# Sheet1.net
KiCad netlist of a schematic drawn in Altium Designer
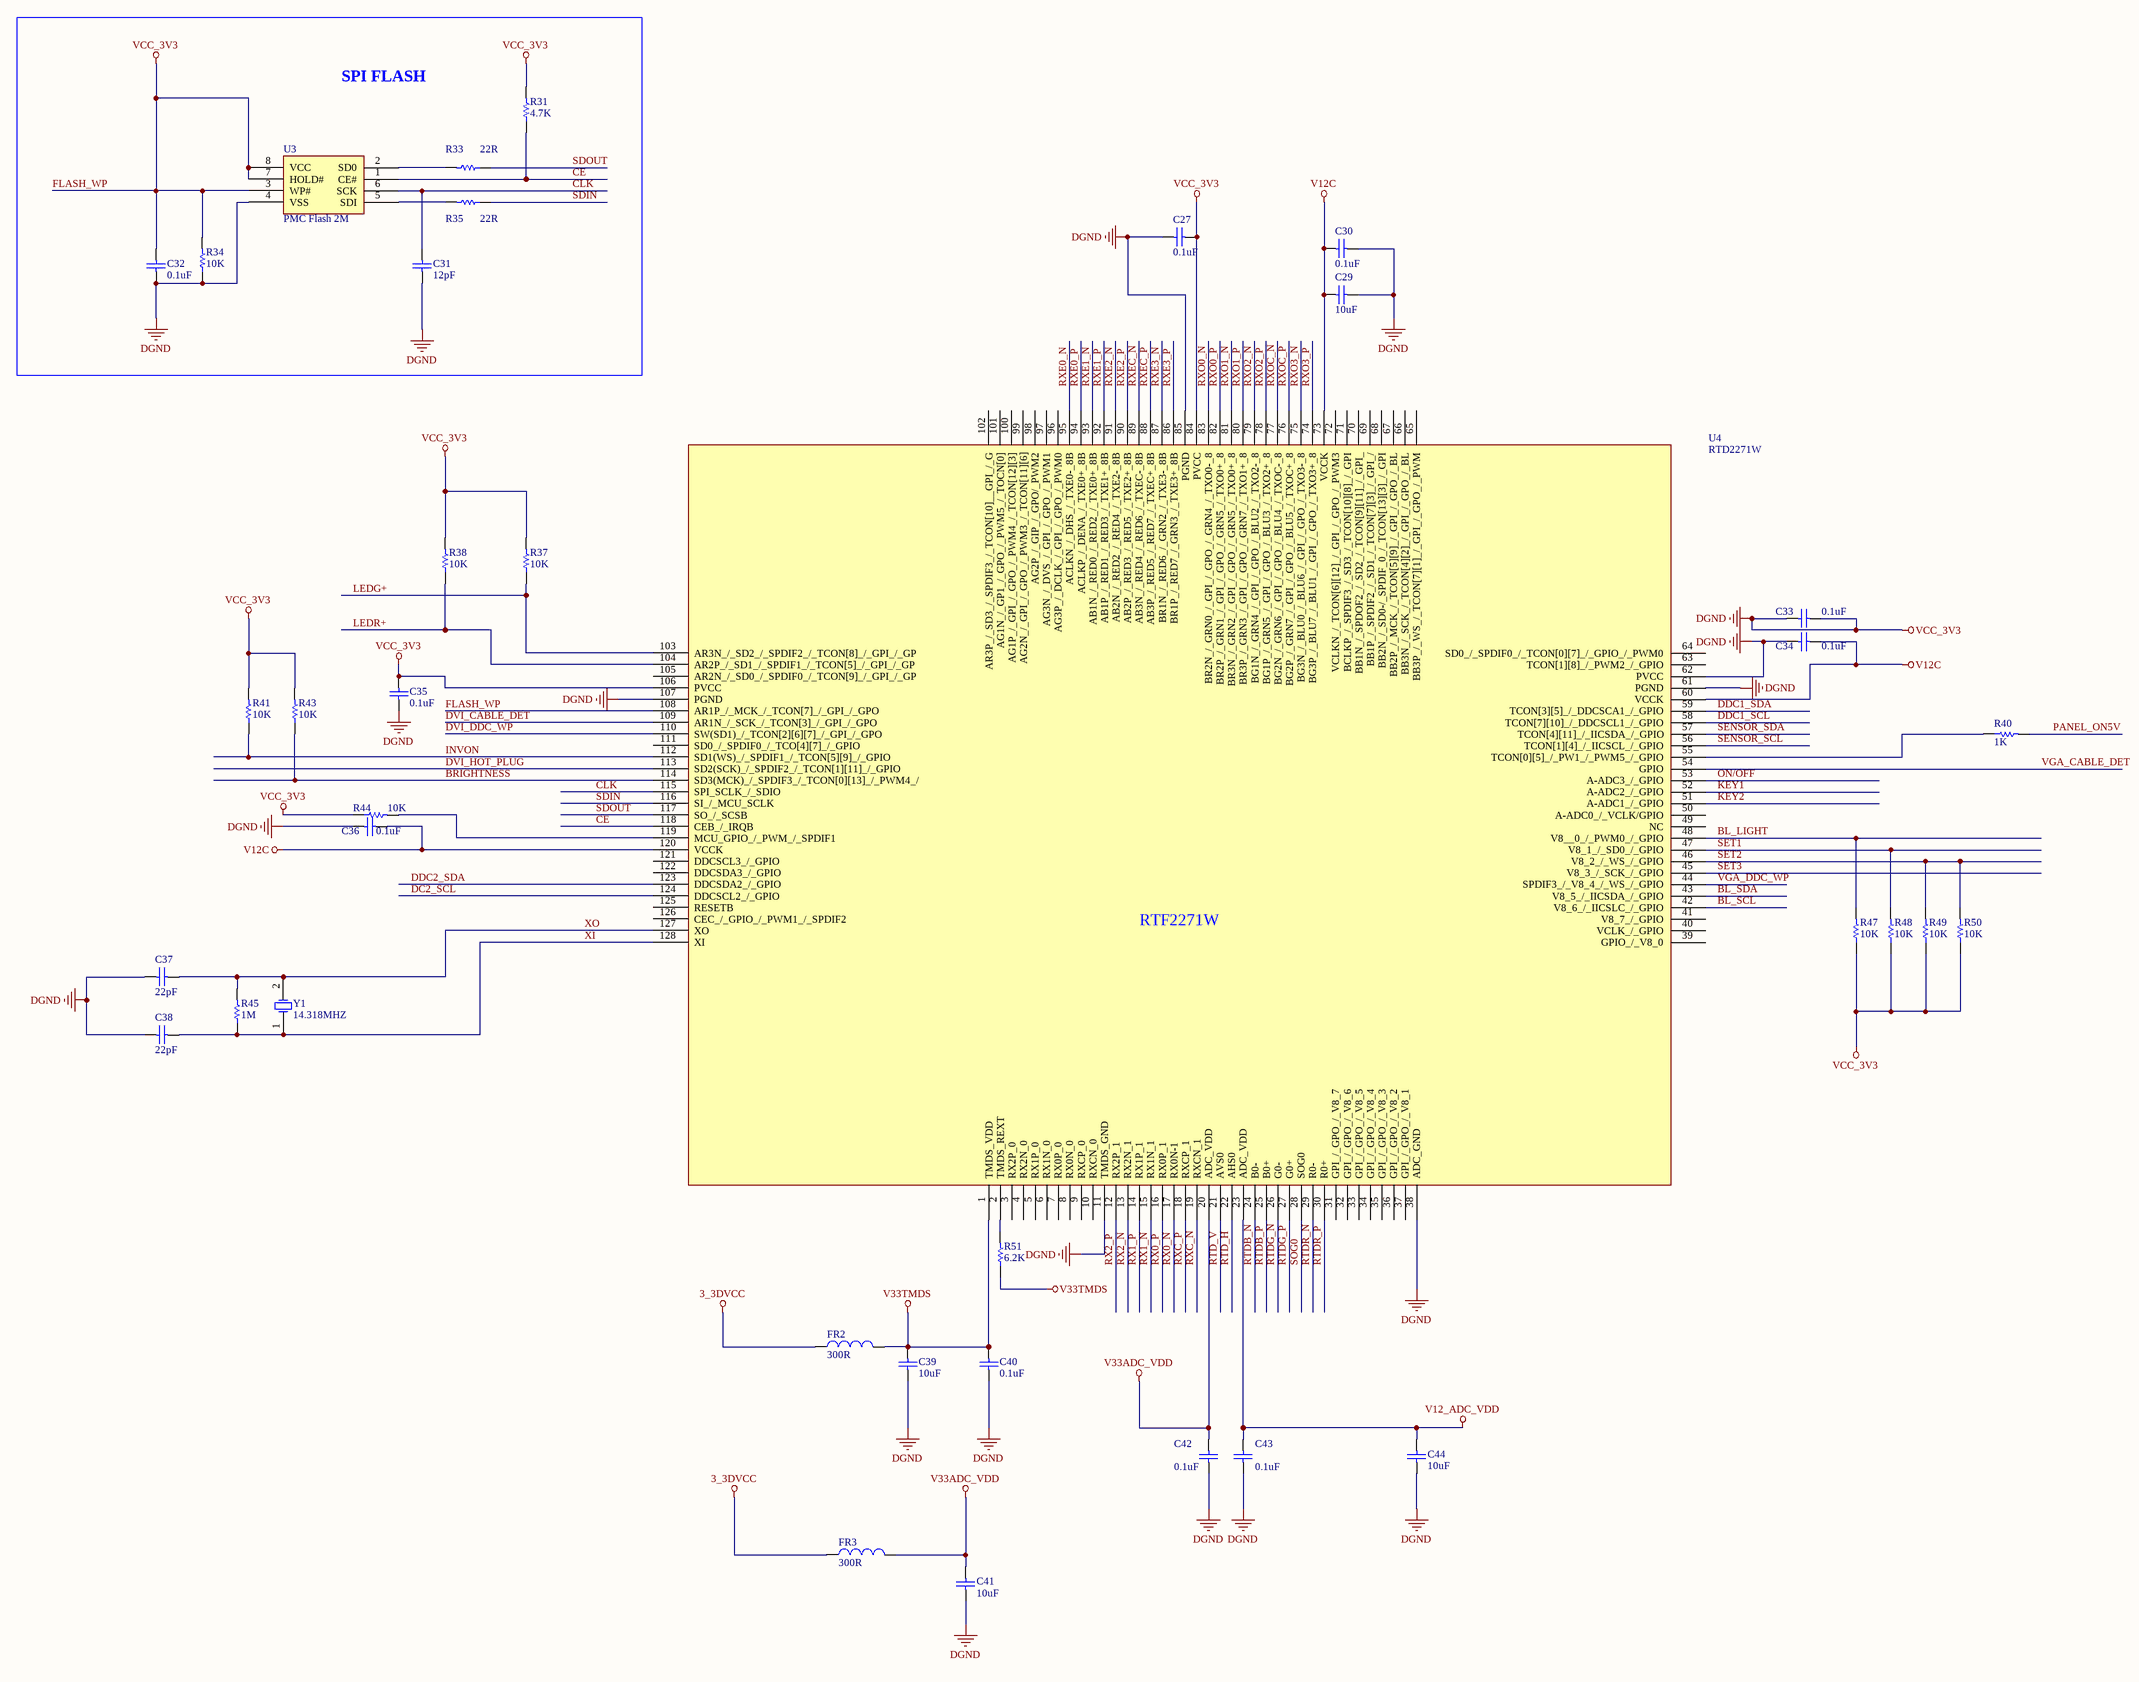
[diagram p0: Sheet1.SchDoc]

(export (version "E")
  (design (tool "Eeschema 10.0.6"))
  (components
    (comp (ref "C27")
      (value "0.1uF")
      (footprint "C-0402")
      (description "Capacitor")
      (fields (field (name "Comment") "Cap") (field (name "PUBLISHER") "Altium Limited"))
      (libsource (lib "Miscellaneous Devices") (part "Cap"))
    )
    (comp (ref "C29")
      (value "10uF")
      (footprint "C-0402")
      (description "Capacitor")
      (fields (field (name "Comment") "Cap") (field (name "PUBLISHER") "Altium Limited"))
      (libsource (lib "Miscellaneous Devices") (part "Cap"))
    )
    (comp (ref "C30")
      (value "0.1uF")
      (footprint "C-0402")
      (description "Capacitor")
      (fields (field (name "Comment") "Cap") (field (name "PUBLISHER") "Altium Limited"))
      (libsource (lib "Miscellaneous Devices") (part "Cap"))
    )
    (comp (ref "C31")
      (value "12pF")
      (footprint "C-0402")
      (description "Capacitor")
      (fields (field (name "Comment") "Cap") (field (name "PUBLISHER") "Altium Limited"))
      (libsource (lib "Miscellaneous Devices") (part "Cap"))
    )
    (comp (ref "C32")
      (value "0.1uF")
      (footprint "C-0402")
      (description "Capacitor")
      (fields (field (name "Comment") "Cap") (field (name "PUBLISHER") "Altium Limited"))
      (libsource (lib "Miscellaneous Devices") (part "Cap"))
    )
    (comp (ref "C33")
      (value "0.1uF")
      (footprint "C-0402")
      (description "Capacitor")
      (fields (field (name "Comment") "Cap") (field (name "PUBLISHER") "Altium Limited"))
      (libsource (lib "Miscellaneous Devices") (part "Cap"))
    )
    (comp (ref "C34")
      (value "0.1uF")
      (footprint "C-0402")
      (description "Capacitor")
      (fields (field (name "Comment") "Cap") (field (name "PUBLISHER") "Altium Limited"))
      (libsource (lib "Miscellaneous Devices") (part "Cap"))
    )
    (comp (ref "C35")
      (value "0.1uF")
      (footprint "C-0402")
      (description "Capacitor")
      (fields (field (name "Comment") "Cap") (field (name "PUBLISHER") "Altium Limited"))
      (libsource (lib "Miscellaneous Devices") (part "Cap"))
    )
    (comp (ref "C36")
      (value "0.1uF")
      (footprint "C-0402")
      (description "Capacitor")
      (fields (field (name "Comment") "Cap") (field (name "PUBLISHER") "Altium Limited"))
      (libsource (lib "Miscellaneous Devices") (part "Cap"))
    )
    (comp (ref "C37")
      (value "22pF")
      (footprint "C-0402")
      (description "Capacitor")
      (fields (field (name "Comment") "Cap") (field (name "PUBLISHER") "Altium Limited"))
      (libsource (lib "Miscellaneous Devices") (part "Cap"))
    )
    (comp (ref "C38")
      (value "22pF")
      (footprint "C-0402")
      (description "Capacitor")
      (fields (field (name "Comment") "Cap") (field (name "PUBLISHER") "Altium Limited"))
      (libsource (lib "Miscellaneous Devices") (part "Cap"))
    )
    (comp (ref "C39")
      (value "10uF")
      (footprint "C-0402")
      (description "Capacitor")
      (fields (field (name "Comment") "Cap") (field (name "PUBLISHER") "Altium Limited"))
      (libsource (lib "Miscellaneous Devices") (part "Cap"))
    )
    (comp (ref "C40")
      (value "0.1uF")
      (footprint "C-0402")
      (description "Capacitor")
      (fields (field (name "Comment") "Cap") (field (name "PUBLISHER") "Altium Limited"))
      (libsource (lib "Miscellaneous Devices") (part "Cap"))
    )
    (comp (ref "C41")
      (value "10uF")
      (footprint "C-0402")
      (description "Capacitor")
      (fields (field (name "Comment") "Cap") (field (name "PUBLISHER") "Altium Limited"))
      (libsource (lib "Miscellaneous Devices") (part "Cap"))
    )
    (comp (ref "C42")
      (value "0.1uF")
      (footprint "C-0402")
      (description "Capacitor")
      (fields (field (name "Comment") "Cap") (field (name "PUBLISHER") "Altium Limited"))
      (libsource (lib "Miscellaneous Devices") (part "Cap"))
    )
    (comp (ref "C43")
      (value "0.1uF")
      (footprint "C-0402")
      (description "Capacitor")
      (fields (field (name "Comment") "Cap") (field (name "PUBLISHER") "Altium Limited"))
      (libsource (lib "Miscellaneous Devices") (part "Cap"))
    )
    (comp (ref "C44")
      (value "10uF")
      (footprint "C-0402")
      (description "Capacitor")
      (fields (field (name "Comment") "Cap") (field (name "PUBLISHER") "Altium Limited"))
      (libsource (lib "Miscellaneous Devices") (part "Cap"))
    )
    (comp (ref "FR2")
      (value "300R")
      (footprint "INDC4532")
      (description "Inductor")
      (fields (field (name "PUBLISHER") "Altium Limited"))
      (libsource (lib "Miscellaneous Devices") (part "Inductor"))
    )
    (comp (ref "FR3")
      (value "300R")
      (footprint "INDC4532")
      (description "Inductor")
      (fields (field (name "PUBLISHER") "Altium Limited"))
      (libsource (lib "Miscellaneous Devices") (part "Inductor"))
    )
    (comp (ref "R31")
      (value "4.7K")
      (footprint "R-0603")
      (description "Resistor")
      (fields (field (name "Comment") "Res1") (field (name "PUBLISHER") "Altium Limited"))
      (libsource (lib "Miscellaneous Devices") (part "Res1"))
    )
    (comp (ref "R33")
      (value "22R")
      (footprint "R-0603")
      (description "Resistor")
      (fields (field (name "Comment") "Res1") (field (name "PUBLISHER") "Altium Limited"))
      (libsource (lib "Miscellaneous Devices") (part "Res1"))
    )
    (comp (ref "R34")
      (value "10K")
      (footprint "R-0603")
      (description "Resistor")
      (fields (field (name "Comment") "Res1") (field (name "PUBLISHER") "Altium Limited"))
      (libsource (lib "Miscellaneous Devices") (part "Res1"))
    )
    (comp (ref "R35")
      (value "22R")
      (footprint "R-0603")
      (description "Resistor")
      (fields (field (name "Comment") "Res1") (field (name "PUBLISHER") "Altium Limited"))
      (libsource (lib "Miscellaneous Devices") (part "Res1"))
    )
    (comp (ref "R37")
      (value "10K")
      (footprint "R-0603")
      (description "Resistor")
      (fields (field (name "Comment") "Res1") (field (name "PUBLISHER") "Altium Limited"))
      (libsource (lib "Miscellaneous Devices") (part "Res1"))
    )
    (comp (ref "R38")
      (value "10K")
      (footprint "R-0603")
      (description "Resistor")
      (fields (field (name "Comment") "Res1") (field (name "PUBLISHER") "Altium Limited"))
      (libsource (lib "Miscellaneous Devices") (part "Res1"))
    )
    (comp (ref "R40")
      (value "1K")
      (footprint "R-0603")
      (description "Resistor")
      (fields (field (name "Comment") "Res1") (field (name "PUBLISHER") "Altium Limited"))
      (libsource (lib "Miscellaneous Devices") (part "Res1"))
    )
    (comp (ref "R41")
      (value "10K")
      (footprint "R-0603")
      (description "Resistor")
      (fields (field (name "Comment") "Res1") (field (name "PUBLISHER") "Altium Limited"))
      (libsource (lib "Miscellaneous Devices") (part "Res1"))
    )
    (comp (ref "R43")
      (value "10K")
      (footprint "R-0603")
      (description "Resistor")
      (fields (field (name "Comment") "Res1") (field (name "PUBLISHER") "Altium Limited"))
      (libsource (lib "Miscellaneous Devices") (part "Res1"))
    )
    (comp (ref "R44")
      (value "10K")
      (footprint "R-0603")
      (description "Resistor")
      (fields (field (name "Comment") "Res1") (field (name "PUBLISHER") "Altium Limited"))
      (libsource (lib "Miscellaneous Devices") (part "Res1"))
    )
    (comp (ref "R45")
      (value "1M")
      (footprint "R-0603")
      (description "Resistor")
      (fields (field (name "Comment") "Res1") (field (name "PUBLISHER") "Altium Limited"))
      (libsource (lib "Miscellaneous Devices") (part "Res1"))
    )
    (comp (ref "R47")
      (value "10K")
      (footprint "R-0603")
      (description "Resistor")
      (fields (field (name "Comment") "Res1") (field (name "PUBLISHER") "Altium Limited"))
      (libsource (lib "Miscellaneous Devices") (part "Res1"))
    )
    (comp (ref "R48")
      (value "10K")
      (footprint "R-0603")
      (description "Resistor")
      (fields (field (name "Comment") "Res1") (field (name "PUBLISHER") "Altium Limited"))
      (libsource (lib "Miscellaneous Devices") (part "Res1"))
    )
    (comp (ref "R49")
      (value "10K")
      (footprint "R-0603")
      (description "Resistor")
      (fields (field (name "Comment") "Res1") (field (name "PUBLISHER") "Altium Limited"))
      (libsource (lib "Miscellaneous Devices") (part "Res1"))
    )
    (comp (ref "R50")
      (value "10K")
      (footprint "R-0603")
      (description "Resistor")
      (fields (field (name "Comment") "Res1") (field (name "PUBLISHER") "Altium Limited"))
      (libsource (lib "Miscellaneous Devices") (part "Res1"))
    )
    (comp (ref "R51")
      (value "6.2K")
      (footprint "R-0603")
      (description "Resistor")
      (fields (field (name "Comment") "Res1") (field (name "PUBLISHER") "Altium Limited"))
      (libsource (lib "Miscellaneous Devices") (part "Res1"))
    )
    (comp (ref "U3")
      (value "PMC Flash 2M")
      (footprint "U-SOP/1.3")
      (libsource (lib "Schlib1") (part "PMC Flash2M"))
    )
    (comp (ref "U4")
      (value "RTD2271W")
      (footprint "U-QFP128/0.5")
      (description "驱动板 主板")
      (libsource (lib "Schlib1") (part "RTD2271W"))
    )
    (comp (ref "Y1")
      (value "14.318MHZ")
      (footprint "Y-DH5")
      (description "Crystal Oscillator")
      (fields (field (name "PUBLISHER") "Altium Limited"))
      (libsource (lib "Miscellaneous Devices") (part "XTAL"))
    )
  )
  (nets
    (net (code "1") (name "/BL_LIGHT") (class "Default")
      (node (ref "R47") (pin "2") (pinfunction "2_2") (pintype "passive"))
      (node (ref "U4") (pin "48") (pinfunction "V8__0_/_PWM0_/_GPIO_48") (pintype "passive"))
    )
    (net (code "2") (name "/BL_SCL") (class "Default")
      (node (ref "U4") (pin "42") (pinfunction "V8_6_/_IICSLC_/_GPIO_42") (pintype "passive"))
    )
    (net (code "3") (name "/BL_SDA") (class "Default")
      (node (ref "U4") (pin "43") (pinfunction "V8_5_/_IICSDA_/_GPIO_43") (pintype "passive"))
    )
    (net (code "4") (name "/BRIGHTNESS") (class "Default")
      (node (ref "R43") (pin "1") (pinfunction "1_1") (pintype "passive"))
      (node (ref "U4") (pin "114") (pinfunction "SD3(MCK)_/_SPDIF3_/_TCON[0][13]_/_PWM4_/_114") (pintype "passive"))
    )
    (net (code "5") (name "/CE") (class "Default")
      (node (ref "R31") (pin "1") (pinfunction "1_1") (pintype "passive"))
      (node (ref "U3") (pin "1") (pinfunction "CE#_1") (pintype "passive"))
      (node (ref "U4") (pin "118") (pinfunction "CEB_/_IRQB_118") (pintype "passive"))
    )
    (net (code "6") (name "/CLK") (class "Default")
      (node (ref "C31") (pin "2") (pinfunction "2_2") (pintype "passive"))
      (node (ref "U3") (pin "6") (pinfunction "SCK_6") (pintype "passive"))
      (node (ref "U4") (pin "115") (pinfunction "SPI_SCLK_/_SDIO_115") (pintype "passive"))
    )
    (net (code "7") (name "/DC2_SCL") (class "Default")
      (node (ref "U4") (pin "124") (pinfunction "DDCSCL2_/_GPIO_124") (pintype "passive"))
    )
    (net (code "8") (name "/DDC1_SCL") (class "Default")
      (node (ref "U4") (pin "58") (pinfunction "TCON[7][10]_/_DDCSCL1_/_GPIO_58") (pintype "passive"))
    )
    (net (code "9") (name "/DDC1_SDA") (class "Default")
      (node (ref "U4") (pin "59") (pinfunction "TCON[3][5]_/_DDCSCA1_/_GPIO_59") (pintype "passive"))
    )
    (net (code "10") (name "/DDC2_SDA") (class "Default")
      (node (ref "U4") (pin "123") (pinfunction "DDCSDA2_/_GPIO_123") (pintype "passive"))
    )
    (net (code "11") (name "/DVI_CABLE_DET") (class "Default")
      (node (ref "U4") (pin "109") (pinfunction "AR1N_/_SCK_/_TCON[3]_/_GPI_/_GPO_109") (pintype "passive"))
    )
    (net (code "12") (name "/DVI_DDC_WP") (class "Default")
      (node (ref "U4") (pin "110") (pinfunction "SW(SD1)_/_TCON[2][6][7]_/_GPI_/_GPO_110") (pintype "passive"))
    )
    (net (code "13") (name "/DVI_HOT_PLUG") (class "Default")
      (node (ref "U4") (pin "113") (pinfunction "SD2(SCK)_/_SPDIF2_/_TCON[1][11]_/_GPIO_113") (pintype "passive"))
    )
    (net (code "14") (name "/INVON") (class "Default")
      (node (ref "R41") (pin "1") (pinfunction "1_1") (pintype "passive"))
      (node (ref "U4") (pin "112") (pinfunction "SD1(WS)_/_SPDIF1_/_TCON[5][9]_/_GPIO_112") (pintype "passive"))
    )
    (net (code "15") (name "/KEY1") (class "Default")
      (node (ref "U4") (pin "52") (pinfunction "A-ADC2_/_GPIO_52") (pintype "passive"))
    )
    (net (code "16") (name "/KEY2") (class "Default")
      (node (ref "U4") (pin "51") (pinfunction "A-ADC1_/_GPIO_51") (pintype "passive"))
    )
    (net (code "17") (name "/LEDG+") (class "Default")
      (node (ref "R37") (pin "1") (pinfunction "1_1") (pintype "passive"))
      (node (ref "U4") (pin "103") (pinfunction "AR3N_/_SD2_/_SPDIF2_/_TCON[8]_/_GPI_/_GP_103") (pintype "passive"))
    )
    (net (code "18") (name "/LEDR+") (class "Default")
      (node (ref "R38") (pin "1") (pinfunction "1_1") (pintype "passive"))
      (node (ref "U4") (pin "104") (pinfunction "AR2P_/_SD1_/_SPDIF1_/_TCON[5]_/_GPI_/_GP_104") (pintype "passive"))
    )
    (net (code "19") (name "/ON{slash}OFF") (class "Default")
      (node (ref "U4") (pin "53") (pinfunction "A-ADC3_/_GPIO_53") (pintype "passive"))
    )
    (net (code "20") (name "/PANEL_ON5V") (class "Default")
      (node (ref "R40") (pin "2") (pinfunction "2_2") (pintype "passive"))
    )
    (net (code "21") (name "/RTDB_N") (class "Default")
      (node (ref "U4") (pin "24") (pinfunction "B0-_24") (pintype "passive"))
    )
    (net (code "22") (name "/RTDB_P") (class "Default")
      (node (ref "U4") (pin "25") (pinfunction "B0+_25") (pintype "passive"))
    )
    (net (code "23") (name "/RTDG_N") (class "Default")
      (node (ref "U4") (pin "26") (pinfunction "G0-_26") (pintype "passive"))
    )
    (net (code "24") (name "/RTDG_P") (class "Default")
      (node (ref "U4") (pin "27") (pinfunction "G0+_27") (pintype "passive"))
    )
    (net (code "25") (name "/RTDR_N") (class "Default")
      (node (ref "U4") (pin "29") (pinfunction "R0-_29") (pintype "passive"))
    )
    (net (code "26") (name "/RTDR_P") (class "Default")
      (node (ref "U4") (pin "30") (pinfunction "R0+_30") (pintype "passive"))
    )
    (net (code "27") (name "/RTD_H") (class "Default")
      (node (ref "U4") (pin "22") (pinfunction "AHS0_22") (pintype "passive"))
    )
    (net (code "28") (name "/RTD_V") (class "Default")
      (node (ref "U4") (pin "21") (pinfunction "AVS0_21") (pintype "passive"))
    )
    (net (code "29") (name "/RX0_N") (class "Default")
      (node (ref "U4") (pin "17") (pinfunction "RX0N-1_17") (pintype "passive"))
    )
    (net (code "30") (name "/RX0_P") (class "Default")
      (node (ref "U4") (pin "16") (pinfunction "RX0P_1_16") (pintype "passive"))
    )
    (net (code "31") (name "/RX1_N") (class "Default")
      (node (ref "U4") (pin "15") (pinfunction "RX1N_1_15") (pintype "passive"))
    )
    (net (code "32") (name "/RX1_P") (class "Default")
      (node (ref "U4") (pin "14") (pinfunction "RX1P_1_14") (pintype "passive"))
    )
    (net (code "33") (name "/RX2_N") (class "Default")
      (node (ref "U4") (pin "13") (pinfunction "RX2N_1_13") (pintype "passive"))
    )
    (net (code "34") (name "/RX2_P") (class "Default")
      (node (ref "U4") (pin "12") (pinfunction "RX2P_1_12") (pintype "passive"))
    )
    (net (code "35") (name "/RXC_N") (class "Default")
      (node (ref "U4") (pin "19") (pinfunction "RXCN_1_19") (pintype "passive"))
    )
    (net (code "36") (name "/RXC_P") (class "Default")
      (node (ref "U4") (pin "18") (pinfunction "RXCP_1_18") (pintype "passive"))
    )
    (net (code "37") (name "/RXE0_N") (class "Default")
      (node (ref "U4") (pin "95") (pinfunction "ACLKN_/_DHS_/_TXE0-_8B_95") (pintype "passive"))
    )
    (net (code "38") (name "/RXE0_P") (class "Default")
      (node (ref "U4") (pin "94") (pinfunction "ACLKP_/_DENA_/_TXE0+_8B_94") (pintype "passive"))
    )
    (net (code "39") (name "/RXE1_N") (class "Default")
      (node (ref "U4") (pin "93") (pinfunction "AB1N_/_RED0_/_RED2_/_TXE0+_8B_93") (pintype "passive"))
    )
    (net (code "40") (name "/RXE1_P") (class "Default")
      (node (ref "U4") (pin "92") (pinfunction "AB1P_/_RED1_/_RED3_/_TXE1+_8B_92") (pintype "passive"))
    )
    (net (code "41") (name "/RXE2_N") (class "Default")
      (node (ref "U4") (pin "91") (pinfunction "AB2N_/_RED2_/_RED4_/_TXE2-_8B_91") (pintype "passive"))
    )
    (net (code "42") (name "/RXE2_P") (class "Default")
      (node (ref "U4") (pin "90") (pinfunction "AB2P_/_RED3_/_RED5_/_TXE2+_8B_90") (pintype "passive"))
    )
    (net (code "43") (name "/RXE3_N") (class "Default")
      (node (ref "U4") (pin "87") (pinfunction "BR1N_/_RED6_/_GRN2_/_TXE3-_8B_87") (pintype "passive"))
    )
    (net (code "44") (name "/RXE3_P") (class "Default")
      (node (ref "U4") (pin "86") (pinfunction "BR1P_/_RED7_/_GRN3_/_TXE3+_8B_86") (pintype "passive"))
    )
    (net (code "45") (name "/RXEC_N") (class "Default")
      (node (ref "U4") (pin "89") (pinfunction "AB3N_/_RED4_/_RED6_/_TXEC-_8B_89") (pintype "passive"))
    )
    (net (code "46") (name "/RXEC_P") (class "Default")
      (node (ref "U4") (pin "88") (pinfunction "AB3P_/_RED5_/_RED7_/_TXEC+_8B_88") (pintype "passive"))
    )
    (net (code "47") (name "/RXO0_N") (class "Default")
      (node (ref "U4") (pin "83") (pinfunction "BR2N_/_GRN0_/_GPI_/_GPO_/_GRN4_/_TXO0-_8_83") (pintype "passive"))
    )
    (net (code "48") (name "/RXO0_P") (class "Default")
      (node (ref "U4") (pin "82") (pinfunction "BR2P_/_GRN1_/_GPI_/_GPO_/_GRN5_/_TXO0+_8_82") (pintype "passive"))
    )
    (net (code "49") (name "/RXO1_N") (class "Default")
      (node (ref "U4") (pin "81") (pinfunction "BR3N_/_GRN2_/_GPI_/_GPO_/_GRN5_/_TXO0+_8_81") (pintype "passive"))
    )
    (net (code "50") (name "/RXO1_P") (class "Default")
      (node (ref "U4") (pin "80") (pinfunction "BR3P_/_GRN3_/_GPI_/_GPO_/_GRN7_/_TXO1+_8_80") (pintype "passive"))
    )
    (net (code "51") (name "/RXO2_N") (class "Default")
      (node (ref "U4") (pin "79") (pinfunction "BG1N_/_GRN4_/_GPI_/_GPO_/_BLU2_/_TXO2-_8_79") (pintype "passive"))
    )
    (net (code "52") (name "/RXO2_P") (class "Default")
      (node (ref "U4") (pin "78") (pinfunction "BG1P_/_GRN5_/_GPI_/_GPO_/_BLU3_/_TXO2+_8_78") (pintype "passive"))
    )
    (net (code "53") (name "/RXO3_N") (class "Default")
      (node (ref "U4") (pin "75") (pinfunction "BG3N_/_BLU0_/_BLU6_/_GPI_/_GPO_/_TXO3-_8_75") (pintype "passive"))
    )
    (net (code "54") (name "/RXO3_P") (class "Default")
      (node (ref "U4") (pin "74") (pinfunction "BG3P_/_BLU7_/_BLU1_/_GPI_/_GPO_/_TXO3+_8_74") (pintype "passive"))
    )
    (net (code "55") (name "/RXOC_N") (class "Default")
      (node (ref "U4") (pin "77") (pinfunction "BG2N_/_GRN6_/_GPI_/_GPO_/_BLU4_/_TXOC-_8_77") (pintype "passive"))
    )
    (net (code "56") (name "/RXOC_P") (class "Default")
      (node (ref "U4") (pin "76") (pinfunction "BG2P_/_GRN7_/_GPI_/_GPO_/_BLU5_/_TXOC+_8_76") (pintype "passive"))
    )
    (net (code "57") (name "/SDIN") (class "Default")
      (node (ref "R35") (pin "1") (pinfunction "1_1") (pintype "passive"))
      (node (ref "U4") (pin "116") (pinfunction "SI_/_MCU_SCLK_116") (pintype "passive"))
    )
    (net (code "58") (name "/SDOUT") (class "Default")
      (node (ref "R33") (pin "1") (pinfunction "1_1") (pintype "passive"))
      (node (ref "U4") (pin "117") (pinfunction "SO_/_SCSB_117") (pintype "passive"))
    )
    (net (code "59") (name "/SENSOR_SCL") (class "Default")
      (node (ref "U4") (pin "56") (pinfunction "TCON[1][4]_/_IICSCL_/_GPIO_56") (pintype "passive"))
    )
    (net (code "60") (name "/SENSOR_SDA") (class "Default")
      (node (ref "U4") (pin "57") (pinfunction "TCON[4][11]_/_IICSDA_/_GPIO_57") (pintype "passive"))
    )
    (net (code "61") (name "/SET1") (class "Default")
      (node (ref "R48") (pin "2") (pinfunction "2_2") (pintype "passive"))
      (node (ref "U4") (pin "47") (pinfunction "V8_1_/_SD0_/_GPIO_47") (pintype "passive"))
    )
    (net (code "62") (name "/SET2") (class "Default")
      (node (ref "R49") (pin "2") (pinfunction "2_2") (pintype "passive"))
      (node (ref "R50") (pin "2") (pinfunction "2_2") (pintype "passive"))
      (node (ref "U4") (pin "46") (pinfunction "V8_2_/_WS_/_GPIO_46") (pintype "passive"))
    )
    (net (code "63") (name "/SET3") (class "Default")
      (node (ref "U4") (pin "45") (pinfunction "V8_3_/_SCK_/_GPIO_45") (pintype "passive"))
    )
    (net (code "64") (name "/SOG0") (class "Default")
      (node (ref "U4") (pin "28") (pinfunction "SOG0_28") (pintype "passive"))
    )
    (net (code "65") (name "/VGA_CABLE_DET") (class "Default")
      (node (ref "U4") (pin "54") (pinfunction "GPIO_54") (pintype "passive"))
    )
    (net (code "66") (name "/VGA_DDC_WP") (class "Default")
      (node (ref "U4") (pin "44") (pinfunction "SPDIF3_/_V8_4_/_WS_/_GPIO_44") (pintype "passive"))
    )
    (net (code "67") (name "/XI") (class "Default")
      (node (ref "C38") (pin "2") (pinfunction "2_2") (pintype "passive"))
      (node (ref "R45") (pin "1") (pinfunction "1_1") (pintype "passive"))
      (node (ref "U4") (pin "128") (pinfunction "XI_128") (pintype "passive"))
      (node (ref "Y1") (pin "1") (pinfunction "OSC1_1") (pintype "passive"))
    )
    (net (code "68") (name "/XO") (class "Default")
      (node (ref "C37") (pin "2") (pinfunction "2_2") (pintype "passive"))
      (node (ref "R45") (pin "2") (pinfunction "2_2") (pintype "passive"))
      (node (ref "U4") (pin "127") (pinfunction "XO_127") (pintype "passive"))
      (node (ref "Y1") (pin "2") (pinfunction "OSC2_2") (pintype "passive"))
    )
    (net (code "69") (name "3_3DVCC") (class "Default")
      (node (ref "FR2") (pin "1") (pinfunction "1_1") (pintype "passive"))
      (node (ref "FR3") (pin "1") (pinfunction "1_1") (pintype "passive"))
    )
    (net (code "70") (name "DGND") (class "Default")
      (node (ref "C27") (pin "1") (pinfunction "1_1") (pintype "passive"))
      (node (ref "C27") (pin "2") (pinfunction "2_2") (pintype "passive"))
      (node (ref "C29") (pin "2") (pinfunction "2_2") (pintype "passive"))
      (node (ref "C30") (pin "2") (pinfunction "2_2") (pintype "passive"))
      (node (ref "C31") (pin "1") (pinfunction "1_1") (pintype "passive"))
      (node (ref "C32") (pin "1") (pinfunction "1_1") (pintype "passive"))
      (node (ref "C32") (pin "2") (pinfunction "2_2") (pintype "passive"))
      (node (ref "C33") (pin "1") (pinfunction "1_1") (pintype "passive"))
      (node (ref "C33") (pin "2") (pinfunction "2_2") (pintype "passive"))
      (node (ref "C34") (pin "1") (pinfunction "1_1") (pintype "passive"))
      (node (ref "C35") (pin "1") (pinfunction "1_1") (pintype "passive"))
      (node (ref "C35") (pin "2") (pinfunction "2_2") (pintype "passive"))
      (node (ref "C36") (pin "1") (pinfunction "1_1") (pintype "passive"))
      (node (ref "C37") (pin "1") (pinfunction "1_1") (pintype "passive"))
      (node (ref "C38") (pin "1") (pinfunction "1_1") (pintype "passive"))
      (node (ref "C39") (pin "1") (pinfunction "1_1") (pintype "passive"))
      (node (ref "C40") (pin "1") (pinfunction "1_1") (pintype "passive"))
      (node (ref "C41") (pin "1") (pinfunction "1_1") (pintype "passive"))
      (node (ref "C42") (pin "1") (pinfunction "1_1") (pintype "passive"))
      (node (ref "C43") (pin "1") (pinfunction "1_1") (pintype "passive"))
      (node (ref "C44") (pin "1") (pinfunction "1_1") (pintype "passive"))
      (node (ref "R31") (pin "2") (pinfunction "2_2") (pintype "passive"))
      (node (ref "R34") (pin "1") (pinfunction "1_1") (pintype "passive"))
      (node (ref "R34") (pin "2") (pinfunction "2_2") (pintype "passive"))
      (node (ref "R37") (pin "2") (pinfunction "2_2") (pintype "passive"))
      (node (ref "R38") (pin "2") (pinfunction "2_2") (pintype "passive"))
      (node (ref "R41") (pin "2") (pinfunction "2_2") (pintype "passive"))
      (node (ref "R43") (pin "2") (pinfunction "2_2") (pintype "passive"))
      (node (ref "R44") (pin "1") (pinfunction "1_1") (pintype "passive"))
      (node (ref "R47") (pin "1") (pinfunction "1_1") (pintype "passive"))
      (node (ref "R48") (pin "1") (pinfunction "1_1") (pintype "passive"))
      (node (ref "R49") (pin "1") (pinfunction "1_1") (pintype "passive"))
      (node (ref "R50") (pin "1") (pinfunction "1_1") (pintype "passive"))
      (node (ref "U3") (pin "3") (pinfunction "WP#_3") (pintype "passive"))
      (node (ref "U3") (pin "4") (pinfunction "VSS_4") (pintype "passive"))
      (node (ref "U3") (pin "7") (pinfunction "HOLD#_7") (pintype "passive"))
      (node (ref "U3") (pin "8") (pinfunction "VCC_8") (pintype "passive"))
      (node (ref "U4") (pin "106") (pinfunction "PVCC_106") (pintype "passive"))
      (node (ref "U4") (pin "107") (pinfunction "PGND_107") (pintype "passive"))
      (node (ref "U4") (pin "108") (pinfunction "AR1P_/_MCK_/_TCON[7]_/_GPI_/_GPO_108") (pintype "passive"))
      (node (ref "U4") (pin "11") (pinfunction "TMDS_GND_11") (pintype "passive"))
      (node (ref "U4") (pin "38") (pinfunction "ADC_GND_38") (pintype "passive"))
      (node (ref "U4") (pin "61") (pinfunction "PGND_61") (pintype "passive"))
      (node (ref "U4") (pin "62") (pinfunction "PVCC_62") (pintype "passive"))
      (node (ref "U4") (pin "84") (pinfunction "PVCC_84") (pintype "passive"))
      (node (ref "U4") (pin "85") (pinfunction "PGND_85") (pintype "passive"))
    )
    (net (code "71") (name "Net-(U3-SD0)") (class "Default")
      (node (ref "R33") (pin "2") (pinfunction "2_2") (pintype "passive"))
      (node (ref "U3") (pin "2") (pinfunction "SD0_2") (pintype "passive"))
    )
    (net (code "72") (name "Net-(U3-SDI)") (class "Default")
      (node (ref "R35") (pin "2") (pinfunction "2_2") (pintype "passive"))
      (node (ref "U3") (pin "5") (pinfunction "SDI_5") (pintype "passive"))
    )
    (net (code "73") (name "Net-(U4-MCU_GPIO_{slash}_PWM_{slash}_SPDIF1)") (class "Default")
      (node (ref "R44") (pin "2") (pinfunction "2_2") (pintype "passive"))
      (node (ref "U4") (pin "119") (pinfunction "MCU_GPIO_/_PWM_/_SPDIF1_119") (pintype "passive"))
    )
    (net (code "74") (name "Net-(U4-TCON[0][5]_{slash}_PW1_{slash}_PWM5_{slash}_GPIO)") (class "Default")
      (node (ref "R40") (pin "1") (pinfunction "1_1") (pintype "passive"))
      (node (ref "U4") (pin "55") (pinfunction "TCON[0][5]_/_PW1_/_PWM5_/_GPIO_55") (pintype "passive"))
    )
    (net (code "75") (name "Net-(U4-TMDS_REXT)") (class "Default")
      (node (ref "R51") (pin "2") (pinfunction "2_2") (pintype "passive"))
      (node (ref "U4") (pin "2") (pinfunction "TMDS_REXT_2") (pintype "passive"))
    )
    (net (code "76") (name "V12C") (class "Default")
      (node (ref "C29") (pin "1") (pinfunction "1_1") (pintype "passive"))
      (node (ref "C30") (pin "1") (pinfunction "1_1") (pintype "passive"))
      (node (ref "C34") (pin "2") (pinfunction "2_2") (pintype "passive"))
      (node (ref "C36") (pin "2") (pinfunction "2_2") (pintype "passive"))
      (node (ref "U4") (pin "120") (pinfunction "VCCK_120") (pintype "passive"))
      (node (ref "U4") (pin "60") (pinfunction "VCCK_60") (pintype "passive"))
      (node (ref "U4") (pin "73") (pinfunction "VCCK_73") (pintype "passive"))
    )
    (net (code "77") (name "V12_ADC_VDD") (class "Default")
      (node (ref "C43") (pin "2") (pinfunction "2_2") (pintype "passive"))
      (node (ref "C44") (pin "2") (pinfunction "2_2") (pintype "passive"))
      (node (ref "U4") (pin "23") (pinfunction "ADC_VDD_23") (pintype "passive"))
    )
    (net (code "78") (name "V33ADC_VDD") (class "Default")
      (node (ref "C41") (pin "2") (pinfunction "2_2") (pintype "passive"))
      (node (ref "C42") (pin "2") (pinfunction "2_2") (pintype "passive"))
      (node (ref "FR3") (pin "2") (pinfunction "2_2") (pintype "passive"))
      (node (ref "U4") (pin "20") (pinfunction "ADC_VDD_20") (pintype "passive"))
    )
    (net (code "79") (name "V33TMDS") (class "Default")
      (node (ref "C39") (pin "2") (pinfunction "2_2") (pintype "passive"))
      (node (ref "C40") (pin "2") (pinfunction "2_2") (pintype "passive"))
      (node (ref "FR2") (pin "2") (pinfunction "2_2") (pintype "passive"))
      (node (ref "R51") (pin "1") (pinfunction "1_1") (pintype "passive"))
      (node (ref "U4") (pin "1") (pinfunction "TMDS_VDD_1") (pintype "passive"))
    )
    (net (code "80") (name "unconnected-(U4-A-ADC0_{slash}_VCLK{slash}GPIO-Pad50)") (class "Default")
      (node (ref "U4") (pin "50") (pinfunction "A-ADC0_/_VCLK/GPIO_50") (pintype "passive"))
    )
    (net (code "81") (name "unconnected-(U4-AG1N_{slash}_GP1_{slash}_GPO_{slash}_PWM5_{slash}_TOCN[0]-Pad101)") (class "Default")
      (node (ref "U4") (pin "101") (pinfunction "AG1N_/_GP1_/_GPO_/_PWM5_/_TOCN[0]_101") (pintype "passive"))
    )
    (net (code "82") (name "unconnected-(U4-AG1P_{slash}_GPI_{slash}_GPO_{slash}_PWM4_{slash}_TCON[12][3]-Pad100)") (class "Default")
      (node (ref "U4") (pin "100") (pinfunction "AG1P_/_GPI_/_GPO_/_PWM4_/_TCON[12][3]_100") (pintype "passive"))
    )
    (net (code "83") (name "unconnected-(U4-AG2N_{slash}_GPI_{slash}_GPO_{slash}_PWM3_{slash}_TCON[11][6]-Pad99)") (class "Default")
      (node (ref "U4") (pin "99") (pinfunction "AG2N_/_GPI_/_GPO_/_PWM3_/_TCON[11][6]_99") (pintype "passive"))
    )
    (net (code "84") (name "unconnected-(U4-AG2P_{slash}_GIP_{slash}_GPO{slash}_PWM2-Pad98)") (class "Default")
      (node (ref "U4") (pin "98") (pinfunction "AG2P_/_GIP_/_GPO/_PWM2_98") (pintype "passive"))
    )
    (net (code "85") (name "unconnected-(U4-AG3N_{slash}_DVS_{slash}_GPI_{slash}_GPO_{slash}_PWM1-Pad97)") (class "Default")
      (node (ref "U4") (pin "97") (pinfunction "AG3N_/_DVS_/_GPI_/_GPO_/_PWM1_97") (pintype "passive"))
    )
    (net (code "86") (name "unconnected-(U4-AG3P_{slash}_DCLK_{slash}_GPI_{slash}_GPO_{slash}_PWM0-Pad96)") (class "Default")
      (node (ref "U4") (pin "96") (pinfunction "AG3P_/_DCLK_/_GPI_/_GPO_/_PWM0_96") (pintype "passive"))
    )
    (net (code "87") (name "unconnected-(U4-AR2N_{slash}_SD0_{slash}_SPDIF0_{slash}_TCON[9]_{slash}_GPI_{slash}_GP-Pad105)") (class "Default")
      (node (ref "U4") (pin "105") (pinfunction "AR2N_/_SD0_/_SPDIF0_/_TCON[9]_/_GPI_/_GP_105") (pintype "passive"))
    )
    (net (code "88") (name "unconnected-(U4-AR3P_{slash}_SD3_{slash}_SPDIF3_{slash}_TCON[10]__GPI_{slash}_G-Pad102)") (class "Default")
      (node (ref "U4") (pin "102") (pinfunction "AR3P_/_SD3_/_SPDIF3_/_TCON[10]__GPI_/_G_102") (pintype "passive"))
    )
    (net (code "89") (name "unconnected-(U4-BB1N_{slash}_SPDOF2_{slash}_SD2_{slash}_TCON[9][11]_{slash}_GPI_-Pad70)") (class "Default")
      (node (ref "U4") (pin "70") (pinfunction "BB1N_/_SPDOF2_/_SD2_/_TCON[9][11]_/_GPI__70") (pintype "passive"))
    )
    (net (code "90") (name "unconnected-(U4-BB1P_{slash}_SPDIF2_{slash}_SD1_{slash}_TCON[7][3]_{slash}_GPI_{slash}-Pad69)") (class "Default")
      (node (ref "U4") (pin "69") (pinfunction "BB1P_/_SPDIF2_/_SD1_/_TCON[7][3]_/_GPI_/_69") (pintype "passive"))
    )
    (net (code "91") (name "unconnected-(U4-BB2N_{slash}_SD0-{slash}_SPDIF_0_{slash}_TCON[13][3]_{slash}_GPI-Pad68)") (class "Default")
      (node (ref "U4") (pin "68") (pinfunction "BB2N_/_SD0-/_SPDIF_0_/_TCON[13][3]_/_GPI_68") (pintype "passive"))
    )
    (net (code "92") (name "unconnected-(U4-BB2P_{slash}_MCK_{slash}_TCON[5][9]_{slash}_GPI_{slash}_GPO_{slash}_BL-Pad67)") (class "Default")
      (node (ref "U4") (pin "67") (pinfunction "BB2P_/_MCK_/_TCON[5][9]_/_GPI_/_GPO_/_BL_67") (pintype "passive"))
    )
    (net (code "93") (name "unconnected-(U4-BB3N_{slash}_SCK_{slash}_TCON[4][2]_{slash}_GPI_{slash}_GPO_{slash}_BL-Pad66)") (class "Default")
      (node (ref "U4") (pin "66") (pinfunction "BB3N_/_SCK_/_TCON[4][2]_/_GPI_/_GPO_/_BL_66") (pintype "passive"))
    )
    (net (code "94") (name "unconnected-(U4-BB3P_{slash}_WS_{slash}_TCON[7][1]_{slash}_GPI_{slash}_GPO_{slash}_PWM-Pad65)") (class "Default")
      (node (ref "U4") (pin "65") (pinfunction "BB3P_/_WS_/_TCON[7][1]_/_GPI_/_GPO_/_PWM_65") (pintype "passive"))
    )
    (net (code "95") (name "unconnected-(U4-BCLKP_{slash}_SPDIF3_{slash}_SD3_{slash}_TCON[10][8]_{slash}_GPI-Pad71)") (class "Default")
      (node (ref "U4") (pin "71") (pinfunction "BCLKP_/_SPDIF3_/_SD3_/_TCON[10][8]_/_GPI_71") (pintype "passive"))
    )
    (net (code "96") (name "unconnected-(U4-CEC_{slash}_GPIO_{slash}_PWM1_{slash}_SPDIF2-Pad126)") (class "Default")
      (node (ref "U4") (pin "126") (pinfunction "CEC_/_GPIO_/_PWM1_/_SPDIF2_126") (pintype "passive"))
    )
    (net (code "97") (name "unconnected-(U4-DDCSCL3_{slash}_GPIO-Pad121)") (class "Default")
      (node (ref "U4") (pin "121") (pinfunction "DDCSCL3_/_GPIO_121") (pintype "passive"))
    )
    (net (code "98") (name "unconnected-(U4-DDCSDA3_{slash}_GPIO-Pad122)") (class "Default")
      (node (ref "U4") (pin "122") (pinfunction "DDCSDA3_/_GPIO_122") (pintype "passive"))
    )
    (net (code "99") (name "unconnected-(U4-GPIO_{slash}_V8_0-Pad39)") (class "Default")
      (node (ref "U4") (pin "39") (pinfunction "GPIO_/_V8_0_39") (pintype "passive"))
    )
    (net (code "100") (name "unconnected-(U4-GPI_{slash}_GPO_{slash}_V8_1-Pad37)") (class "Default")
      (node (ref "U4") (pin "37") (pinfunction "GPI_/_GPO_/_V8_1_37") (pintype "passive"))
    )
    (net (code "101") (name "unconnected-(U4-GPI_{slash}_GPO_{slash}_V8_2-Pad36)") (class "Default")
      (node (ref "U4") (pin "36") (pinfunction "GPI_/_GPO_/_V8_2_36") (pintype "passive"))
    )
    (net (code "102") (name "unconnected-(U4-GPI_{slash}_GPO_{slash}_V8_3-Pad35)") (class "Default")
      (node (ref "U4") (pin "35") (pinfunction "GPI_/_GPO_/_V8_3_35") (pintype "passive"))
    )
    (net (code "103") (name "unconnected-(U4-GPI_{slash}_GPO_{slash}_V8_4-Pad34)") (class "Default")
      (node (ref "U4") (pin "34") (pinfunction "GPI_/_GPO_/_V8_4_34") (pintype "passive"))
    )
    (net (code "104") (name "unconnected-(U4-GPI_{slash}_GPO_{slash}_V8_5-Pad33)") (class "Default")
      (node (ref "U4") (pin "33") (pinfunction "GPI_/_GPO_/_V8_5_33") (pintype "passive"))
    )
    (net (code "105") (name "unconnected-(U4-GPI_{slash}_GPO_{slash}_V8_6-Pad32)") (class "Default")
      (node (ref "U4") (pin "32") (pinfunction "GPI_/_GPO_/_V8_6_32") (pintype "passive"))
    )
    (net (code "106") (name "unconnected-(U4-GPI_{slash}_GPO_{slash}_V8_7-Pad31)") (class "Default")
      (node (ref "U4") (pin "31") (pinfunction "GPI_/_GPO_/_V8_7_31") (pintype "passive"))
    )
    (net (code "107") (name "unconnected-(U4-NC-Pad49)") (class "Default")
      (node (ref "U4") (pin "49") (pinfunction "NC_49") (pintype "passive"))
    )
    (net (code "108") (name "unconnected-(U4-RESETB-Pad125)") (class "Default")
      (node (ref "U4") (pin "125") (pinfunction "RESETB_125") (pintype "passive"))
    )
    (net (code "109") (name "unconnected-(U4-RX0N_0-Pad8)") (class "Default")
      (node (ref "U4") (pin "8") (pinfunction "RX0N_0_8") (pintype "passive"))
    )
    (net (code "110") (name "unconnected-(U4-RX0P_0-Pad7)") (class "Default")
      (node (ref "U4") (pin "7") (pinfunction "RX0P_0_7") (pintype "passive"))
    )
    (net (code "111") (name "unconnected-(U4-RX1N_0-Pad6)") (class "Default")
      (node (ref "U4") (pin "6") (pinfunction "RX1N_0_6") (pintype "passive"))
    )
    (net (code "112") (name "unconnected-(U4-RX1P_0-Pad5)") (class "Default")
      (node (ref "U4") (pin "5") (pinfunction "RX1P_0_5") (pintype "passive"))
    )
    (net (code "113") (name "unconnected-(U4-RX2N_0-Pad4)") (class "Default")
      (node (ref "U4") (pin "4") (pinfunction "RX2N_0_4") (pintype "passive"))
    )
    (net (code "114") (name "unconnected-(U4-RX2P_0-Pad3)") (class "Default")
      (node (ref "U4") (pin "3") (pinfunction "RX2P_0_3") (pintype "passive"))
    )
    (net (code "115") (name "unconnected-(U4-RXCN_0-Pad10)") (class "Default")
      (node (ref "U4") (pin "10") (pinfunction "RXCN_0_10") (pintype "passive"))
    )
    (net (code "116") (name "unconnected-(U4-RXCP_0-Pad9)") (class "Default")
      (node (ref "U4") (pin "9") (pinfunction "RXCP_0_9") (pintype "passive"))
    )
    (net (code "117") (name "unconnected-(U4-SD0_{slash}_SPDIF0_{slash}_TCON[0][7]_{slash}_GPIO_{slash}_PWM0-Pad64)") (class "Default")
      (node (ref "U4") (pin "64") (pinfunction "SD0_/_SPDIF0_/_TCON[0][7]_/_GPIO_/_PWM0_64") (pintype "passive"))
    )
    (net (code "118") (name "unconnected-(U4-SD0_{slash}_SPDIF0_{slash}_TCO[4][7]_{slash}_GPIO-Pad111)") (class "Default")
      (node (ref "U4") (pin "111") (pinfunction "SD0_/_SPDIF0_/_TCO[4][7]_/_GPIO_111") (pintype "passive"))
    )
    (net (code "119") (name "unconnected-(U4-TCON[1][8]_{slash}_PWM2_{slash}_GPIO-Pad63)") (class "Default")
      (node (ref "U4") (pin "63") (pinfunction "TCON[1][8]_/_PWM2_/_GPIO_63") (pintype "passive"))
    )
    (net (code "120") (name "unconnected-(U4-V8_7_{slash}_GPIO-Pad41)") (class "Default")
      (node (ref "U4") (pin "41") (pinfunction "V8_7_/_GPIO_41") (pintype "passive"))
    )
    (net (code "121") (name "unconnected-(U4-VCLKN_{slash}_TCON[6][12]_{slash}_GPI_{slash}_GPO_{slash}_PWM3-Pad72)") (class "Default")
      (node (ref "U4") (pin "72") (pinfunction "VCLKN_/_TCON[6][12]_/_GPI_/_GPO_/_PWM3_72") (pintype "passive"))
    )
    (net (code "122") (name "unconnected-(U4-VCLK_{slash}_GPIO-Pad40)") (class "Default")
      (node (ref "U4") (pin "40") (pinfunction "VCLK_/_GPIO_40") (pintype "passive"))
    )
  )
)
